# SCH2_Power.net
KiCad netlist of a schematic drawn in Altium Designer
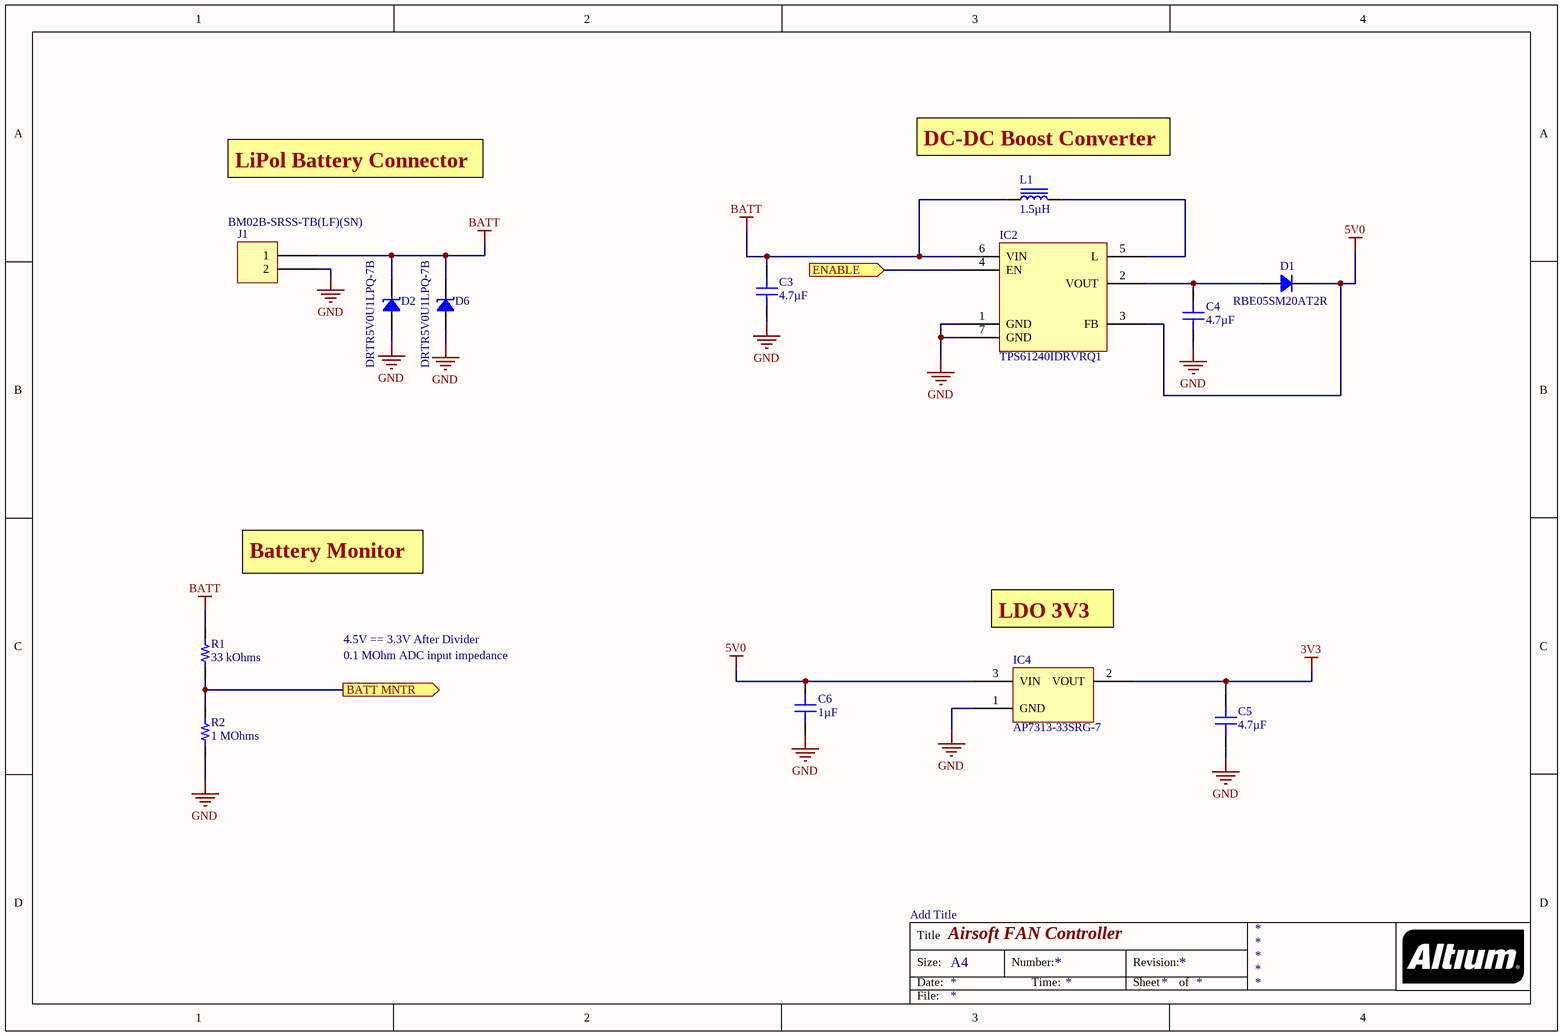
[diagram p0: SCH2_Power.SchDoc]

(export (version "E")
  (design (tool "Eeschema 10.0.6"))
  (components
    (comp (ref "C3")
      (value "4.7µF")
      (footprint "CAP 0402_1005")
      (description "CAP CER 4.7UF 10V X5R 0402")
      (fields
        (field (name "PART NUMBER") "C1005X5R1A475K050BC")
        (field (name "MANUFACTURER") "TDK Corporation")
      )
      (libsource (lib "Celestial Altium Library - altium_library") (part "Capacitor"))
    )
    (comp (ref "C4")
      (value "4.7µF")
      (footprint "CAP 0402_1005")
      (description "CAP CER 4.7UF 10V X5R 0402")
      (fields
        (field (name "PART NUMBER") "C1005X5R1A475K050BC")
        (field (name "MANUFACTURER") "TDK Corporation")
      )
      (libsource (lib "Celestial Altium Library - altium_library") (part "Capacitor"))
    )
    (comp (ref "C5")
      (value "4.7µF")
      (footprint "CAP 0402_1005")
      (description "CAP CER 4.7UF 10V X5R 0402")
      (fields
        (field (name "PART NUMBER") "C1005X5R1A475K050BC")
        (field (name "MANUFACTURER") "TDK Corporation")
      )
      (libsource (lib "Celestial Altium Library - altium_library") (part "Capacitor"))
    )
    (comp (ref "C6")
      (value "1µF")
      (footprint "CAP 0402_1005")
      (description "CAP CER 1UF 6.3V X6S 0402")
      (fields (field (name "PART NUMBER") "JMK105C6105KV-F") (field (name "MANUFACTURER") "Taiyo Yuden"))
      (libsource (lib "Celestial Altium Library - altium_library") (part "Capacitor"))
    )
    (comp (ref "D1")
      (value "RBE05SM20AT2R")
      (footprint "SOD-523")
      (description "DIODE SCHOTTKY 20V 500MA EMD2")
      (fields (field (name "MANUFACTURER") "Rohm Semiconductor"))
      (libsource (lib "Celestial Altium Library - altium_library") (part "Diode"))
    )
    (comp (ref "D2")
      (value "DRTR5V0U1LPQ-7B")
      (footprint "0402")
      (description "DATALINE PROTECT PP X1-DFN1006-2")
      (fields (field (name "MANUFACTURER") "Diodes Incorporated"))
      (libsource (lib "Celestial Altium Library - altium_library") (part "DIODE TVS UNI"))
    )
    (comp (ref "D6")
      (value "DRTR5V0U1LPQ-7B")
      (footprint "0402")
      (description "DATALINE PROTECT PP X1-DFN1006-2")
      (fields (field (name "MANUFACTURER") "Diodes Incorporated"))
      (libsource (lib "Celestial Altium Library - altium_library") (part "DIODE TVS UNI"))
    )
    (comp (ref "IC2")
      (value "TPS61240IDRVRQ1")
      (footprint "TI WSON-6 DRV0006D 2x2MM")
      (description "IC REG BOOST 5V 500MA 6SON")
      (fields (field (name "MANUFACTURER") "Texas Instruments"))
      (libsource (lib "Celestial Altium Library - altium_library") (part "TI TPS6124x DRV"))
    )
    (comp (ref "IC4")
      (value "AP7313-33SRG-7")
      (footprint "DIODES SOT-23-3")
      (description "IC REG LIN 3.3V 150MA SOT23R-3")
      (fields (field (name "MANUFACTURER") "Diodes Incorporated"))
      (libsource (lib "Celestial Altium Library - altium_library") (part "Diodes Inc AP7313R"))
    )
    (comp (ref "J1")
      (value "BM02B-SRSS-TB(LF)(SN)")
      (footprint "MOLX-53398-0271_V")
      (description "CONN HEADER SMD 2POS 1MM")
      (fields (field (name "MANUFACTURER") "JST Sales America Inc."))
      (libsource (lib "Celestial Altium Library - altium_library") (part "2 Pin"))
    )
    (comp (ref "L1")
      (value "1.5µH")
      (footprint "IND 0806_2016")
      (description "FIXED IND 1.5UH 540MA 330 MOHM")
      (fields
        (field (name "PART NUMBER") "LQH2MCN1R5M52L")
        (field (name "MANUFACTURER") "Murata Electronics")
      )
      (libsource (lib "Celestial Altium Library - altium_library") (part "Inductor"))
    )
    (comp (ref "R1")
      (value "33 kOhms")
      (footprint "RES 0402_1005")
      (description "RES SMD 33K OHM 0.5% 1/16W 0402")
      (fields (field (name "PART NUMBER") "RR0510P-333-D") (field (name "MANUFACTURER") "Susumu"))
      (libsource (lib "Celestial Altium Library - altium_library") (part "Resistor"))
    )
    (comp (ref "R2")
      (value "1 MOhms")
      (footprint "RES 0402_1005")
      (description "RES SMD 1M OHM 1% 1/16W 0402")
      (fields (field (name "PART NUMBER") "CRCW04021M00FKTD") (field (name "MANUFACTURER") "Vishay Dale"))
      (libsource (lib "Celestial Altium Library - altium_library") (part "Resistor"))
    )
  )
  (nets
    (net (code "1") (name "/BATT MNTR") (class "Default")
      (node (ref "R1") (pin "1") (pinfunction "1_1") (pintype "passive"))
      (node (ref "R2") (pin "2") (pinfunction "2_2") (pintype "passive"))
    )
    (net (code "2") (name "/ENABLE") (class "Default")
      (node (ref "IC2") (pin "4") (pinfunction "EN_4") (pintype "passive"))
    )
    (net (code "3") (name "3V3") (class "Default")
      (node (ref "C5") (pin "2") (pinfunction "2_2") (pintype "passive"))
      (node (ref "IC4") (pin "2") (pinfunction "VOUT_2") (pintype "passive"))
    )
    (net (code "4") (name "5V0") (class "Default")
      (node (ref "C6") (pin "2") (pinfunction "2_2") (pintype "passive"))
      (node (ref "D1") (pin "2") (pinfunction "2_2") (pintype "passive"))
      (node (ref "IC2") (pin "3") (pinfunction "FB_3") (pintype "passive"))
      (node (ref "IC4") (pin "3") (pinfunction "VIN_3") (pintype "passive"))
    )
    (net (code "5") (name "BATT") (class "Default")
      (node (ref "C3") (pin "2") (pinfunction "2_2") (pintype "passive"))
      (node (ref "D2") (pin "2") (pinfunction "2_2") (pintype "passive"))
      (node (ref "D6") (pin "2") (pinfunction "2_2") (pintype "passive"))
      (node (ref "IC2") (pin "6") (pinfunction "VIN_6") (pintype "passive"))
      (node (ref "J1") (pin "1") (pinfunction "1_1") (pintype "passive"))
      (node (ref "L1") (pin "1") (pinfunction "1_1") (pintype "passive"))
      (node (ref "R1") (pin "2") (pinfunction "2_2") (pintype "passive"))
    )
    (net (code "6") (name "GND") (class "Default")
      (node (ref "C3") (pin "1") (pinfunction "1_1") (pintype "passive"))
      (node (ref "C4") (pin "1") (pinfunction "1_1") (pintype "passive"))
      (node (ref "C5") (pin "1") (pinfunction "1_1") (pintype "passive"))
      (node (ref "C6") (pin "1") (pinfunction "1_1") (pintype "passive"))
      (node (ref "D2") (pin "1") (pinfunction "1_1") (pintype "passive"))
      (node (ref "D6") (pin "1") (pinfunction "1_1") (pintype "passive"))
      (node (ref "IC2") (pin "1") (pinfunction "GND_1") (pintype "passive"))
      (node (ref "IC2") (pin "7") (pinfunction "GND_7") (pintype "passive"))
      (node (ref "IC4") (pin "1") (pinfunction "GND_1") (pintype "passive"))
      (node (ref "J1") (pin "2") (pinfunction "2_2") (pintype "passive"))
      (node (ref "R2") (pin "1") (pinfunction "1_1") (pintype "passive"))
    )
    (net (code "7") (name "Net-(IC2-L)") (class "Default")
      (node (ref "IC2") (pin "5") (pinfunction "L_5") (pintype "passive"))
      (node (ref "L1") (pin "2") (pinfunction "2_2") (pintype "passive"))
    )
    (net (code "8") (name "Net-(IC2-VOUT)") (class "Default")
      (node (ref "C4") (pin "2") (pinfunction "2_2") (pintype "passive"))
      (node (ref "D1") (pin "1") (pinfunction "1_1") (pintype "passive"))
      (node (ref "IC2") (pin "2") (pinfunction "VOUT_2") (pintype "passive"))
    )
  )
)
